# oes-r2.net
KiCad netlist of a schematic drawn in EAGLE
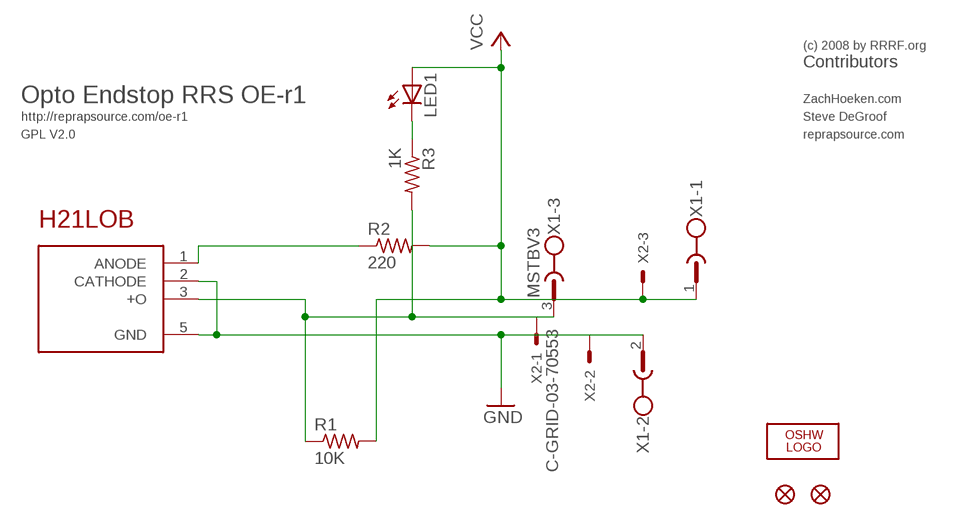
[diagram p0: schematic, sheet 1]

(export (version "E")
  (design (tool "Eeschema 10.0.6"))
  (components
    (comp (ref "JP1")
      (value "FIDUCIAL1X2")
      (footprint "eagle-import:FIDUCIAL-1X2")
      (libsource (lib "eagle-import") (part "FIDUCIAL1X2"))
    )
    (comp (ref "JP2")
      (value "FIDUCIAL1X2")
      (footprint "eagle-import:FIDUCIAL-1X2")
      (libsource (lib "eagle-import") (part "FIDUCIAL1X2"))
    )
    (comp (ref "LED1")
      (value "LEDCHIP-LED0805")
      (footprint "eagle-import:CHIP-LED0805")
      (libsource (lib "eagle-import") (part "LEDCHIP-LED0805"))
    )
    (comp (ref "LOGO1")
      (value "OSHW_LOGO_6MILX0100-NT")
      (footprint "eagle-import:OSHW_6X100_NOTEXT")
      (libsource (lib "eagle-import") (part "OSHW_LOGO_6MILX0100-NT"))
    )
    (comp (ref "R1")
      (value "10K")
      (footprint "eagle-import:R0603")
      (libsource (lib "eagle-import") (part "R-US_R0603"))
    )
    (comp (ref "R2")
      (value "220")
      (footprint "eagle-import:R0603")
      (libsource (lib "eagle-import") (part "R-US_R0603"))
    )
    (comp (ref "R3")
      (value "1K")
      (footprint "eagle-import:R0603")
      (libsource (lib "eagle-import") (part "R-US_R0603"))
    )
    (comp (ref "U1")
      (value "H21LOB")
      (footprint "eagle-import:H21")
      (libsource (lib "eagle-import") (part "H21LOB"))
    )
    (comp (ref "X1")
      (value "MSTBV3")
      (footprint "eagle-import:MSTBV3")
      (fields (field (name "MPN") "MSTBV 2,5/3-GF-5.08"))
      (libsource (lib "eagle-import") (part "MSTBV3"))
    )
    (comp (ref "X2")
      (value "C-GRID-03-70553")
      (footprint "eagle-import:70553-03")
      (libsource (lib "eagle-import") (part "C-GRID-03-70553"))
    )
  )
  (nets
    (net (code "1") (name "GND") (class "Default")
      (node (ref "U1") (pin "2") (pinfunction "CATHODE_2") (pintype "bidirectional"))
      (node (ref "U1") (pin "5") (pinfunction "GND_5") (pintype "bidirectional"))
      (node (ref "X1") (pin "2") (pinfunction "1_2") (pintype "passive"))
      (node (ref "X2") (pin "2") (pinfunction "S_2") (pintype "passive"))
    )
    (net (code "2") (name "Net-(LED1-PadC)") (class "Default")
      (node (ref "LED1") (pin "C") (pinfunction "C_C") (pintype "passive"))
      (node (ref "R3") (pin "1") (pinfunction "1_1") (pintype "passive"))
    )
    (net (code "3") (name "Net-(U1-+O)") (class "Default")
      (node (ref "R1") (pin "1") (pinfunction "1_1") (pintype "passive"))
      (node (ref "R3") (pin "2") (pinfunction "2_2") (pintype "passive"))
      (node (ref "U1") (pin "3") (pinfunction "+O_3") (pintype "bidirectional"))
      (node (ref "X1") (pin "3") (pinfunction "1_3") (pintype "passive"))
      (node (ref "X2") (pin "1") (pinfunction "S_1") (pintype "passive"))
    )
    (net (code "4") (name "Net-(U1-ANODE)") (class "Default")
      (node (ref "R2") (pin "1") (pinfunction "1_1") (pintype "passive"))
      (node (ref "U1") (pin "1") (pinfunction "ANODE_1") (pintype "bidirectional"))
    )
    (net (code "5") (name "VCC") (class "Default")
      (node (ref "LED1") (pin "A") (pinfunction "A_A") (pintype "passive"))
      (node (ref "R1") (pin "2") (pinfunction "2_2") (pintype "passive"))
      (node (ref "R2") (pin "2") (pinfunction "2_2") (pintype "passive"))
      (node (ref "X1") (pin "1") (pinfunction "1_1") (pintype "passive"))
      (node (ref "X2") (pin "3") (pinfunction "S_3") (pintype "passive"))
    )
  )
)
